# ELEC5550_Team_26_USB_Schematic.net
KiCad netlist of a schematic drawn in Altium Designer
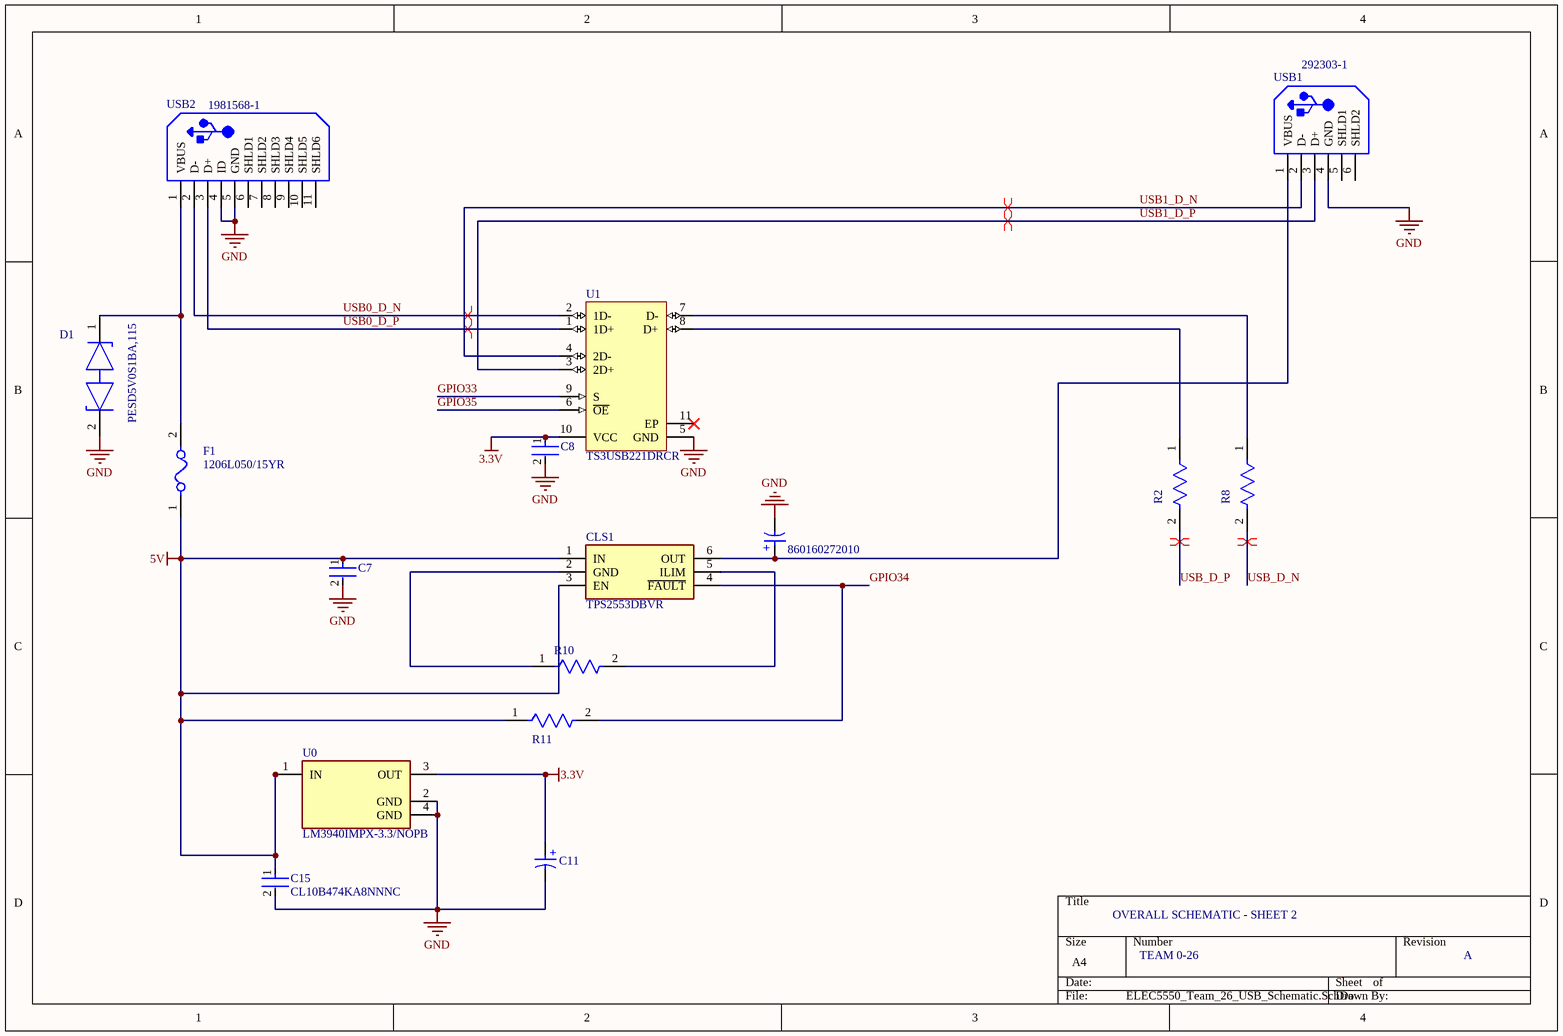
[diagram p0: ELEC5550_Team_26_USB_Schematic.SchDoc]

(export (version "E")
  (design (tool "Eeschema 10.0.6"))
  (components
    (comp (ref "C7")
      (value "CC0805KRX7R9BB104")
      (footprint "FP-CC0805-0_85-MFG")
      (description "CAP CER 0.1UF 50V X7R 0805")
      (fields (field (name "TOLERANCE") "0.1") (field (name "MANUFACTURER") "Yageo"))
      (libsource (lib "Altium Content Vault") (part "11868f565c42a9108669ba33697ecf6"))
    )
    (comp (ref "C8")
      (value "CC0805KRX7R9BB104")
      (footprint "FP-CC0805-0_85-MFG")
      (description "CAP CER 0.1UF 50V X7R 0805")
      (fields (field (name "TOLERANCE") "0.1") (field (name "MANUFACTURER") "Yageo"))
      (libsource (lib "Altium Content Vault") (part "11868f565c42a9108669ba33697ecf6"))
    )
    (comp (ref "C9")
      (value "860160272010")
      (footprint "WCAP-ATLL_D5H11")
      (description "860160272010 Cap, 120Uf, 10V, Alu Elec, Radial Rohs Compliant: Yes")
      (fields (field (name "TOLERANCE") "20%"))
      (libsource (lib "Altium Content Vault") (part "Capacitor_Polarized"))
    )
    (comp (ref "C11")
      (value "KS336M016C07RR0VH2FP0")
      (footprint "WCAP-ATLL_D5H11")
      (description "860160372005 Aluminium Electrolytic Capacitor-Leaded Rohs Compliant: Yes")
      (fields (field (name "TOLERANCE") "20%"))
      (libsource (lib "Altium Content Vault") (part "Capacitor_Polarized"))
    )
    (comp (ref "C15")
      (value "CL10B474KA8NNNC")
      (footprint "FP-GRM188-0_1-e0_2_0_5-MFG")
      (description "25V 470nF X7R ±10% 0603 Multilayer Ceramic Capacitors MLCC - SMD/SMT ROHS")
      (fields (field (name "TOLERANCE") "10%"))
      (libsource (lib "Altium Content Vault") (part "11868f565c42a9108669ba33697ecf6"))
    )
    (comp (ref "CLS1")
      (value "TPS2553DBVR")
      (footprint "SamacSys:SOT95P280X145-6N")
      (description "Integrated Circuit")
      (fields (field (name "MOUSER PART NUMBER") "595-TPS2553DBVR"))
      (libsource (lib "*") (part "TPS2553DBVR"))
    )
    (comp (ref "D1")
      (value "PESD5V0S1BA,115")
      (footprint "FP-SOD323-CA-MFG")
      (description "TVS DIODE 5V 14V SOD323")
      (libsource (lib "Altium Content Vault") (part "f6dbb2535d6b2d347ec798cb4d032a4"))
    )
    (comp (ref "F1")
      (value "1206L050/15YR")
      (footprint "FP-1206L-MFG")
      (description "PTC RESET FUSE 15V 500MA 1206")
      (fields
        (field (name "MANUFACTURER") "Littelfuse Inc")
        (field (name "OCTOPART") "https://octopart.com/1206l050%2F15yr-littelfuse-673645")
      )
      (libsource (lib "Altium Content Vault") (part "5bcf9b9f640e542cf0359d10258e979"))
    )
    (comp (ref "R2")
      (value "RC0603JR-0722RL")
      (footprint "FP-RC0603-0_55-IPC_C")
      (description "RES SMD 22 OHM 5% 1/10W 0603")
      (fields (field (name "TOLERANCE") "5%"))
      (libsource (lib "Altium Content Vault") (part "1029c3af85768c4190bb7ad29bc67b5"))
    )
    (comp (ref "R8")
      (value "RC0603JR-0722RL")
      (footprint "FP-RC0603-0_55-IPC_C")
      (description "RES SMD 22 OHM 5% 1/10W 0603")
      (fields (field (name "TOLERANCE") "5%"))
      (libsource (lib "Altium Content Vault") (part "1029c3af85768c4190bb7ad29bc67b5"))
    )
    (comp (ref "R10")
      (value "RCT0320KJLF")
      (footprint "FP-RT0603-MFG")
      (description "RT0603 20KΩ 0.1W 25 ppm/°C 0.10%")
      (fields (field (name "MANUFACTURER PART NUMBER") "RT0603BRD1320KL") (field (name "TOLERANCE") "0.001"))
      (libsource (lib "Altium Content Vault") (part "1029c3af85768c4190bb7ad29bc67b5"))
    )
    (comp (ref "R11")
      (value "RCT03100KJLF")
      (footprint "FP-AT0603-IPC_A")
      (libsource (lib "Altium Content Vault") (part "1029c3af85768c4190bb7ad29bc67b5"))
    )
    (comp (ref "U0")
      (value "LM3940IMPX-3.3/NOPB")
      (footprint "FP-DCY0004A-MFG")
      (description "IC REG LINEAR 3.3V 1A SOT223-4")
      (libsource (lib "Altium Content Vault") (part "c31ed432f589313beb2aec2175fc138"))
    )
    (comp (ref "U1")
      (value "TS3USB221DRCR")
      (footprint "DRC0010J_V")
      (fields (field (name "MANUFACTURER") "Texas Instruments"))
      (libsource (lib "Altium Content Vault") (part "TI-TS3USB221-SON_DRC-10"))
    )
    (comp (ref "USB1")
      (value "292303-1")
      (footprint "TE-292303-1_V")
      (fields (field (name "MANUFACTURER") "TE Connectivity"))
      (libsource (lib "Altium Content Vault") (part "USB-4-2SHLD"))
    )
    (comp (ref "USB2")
      (value "1981568-1")
      (footprint "TECO-1981568-5_V")
      (description "Micro USB Receptacle Standard Type B Assy, 5-Pin SMD, RoHS, Tape and Reel")
      (fields (field (name "MANUFACTURER") "TE Connectivity"))
      (libsource (lib "Altium Content Vault") (part "USB-5-6SHLD"))
    )
  )
  (nets
    (net (code "1") (name "/GPIO33") (class "Default")
      (node (ref "U1") (pin "9") (pinfunction "S_9") (pintype "input"))
    )
    (net (code "2") (name "/GPIO34") (class "Default")
      (node (ref "CLS1") (pin "4") (pinfunction "~{FAULT}_4") (pintype "passive"))
      (node (ref "R11") (pin "2") (pinfunction "2_2") (pintype "passive"))
    )
    (net (code "3") (name "/GPIO35") (class "Default")
      (node (ref "U1") (pin "6") (pinfunction "~{OE}_6") (pintype "input"))
    )
    (net (code "4") (name "/USB0_D_N") (class "Default")
      (node (ref "U1") (pin "2") (pinfunction "1D-_2") (pintype "bidirectional"))
      (node (ref "USB2") (pin "2") (pinfunction "D-_2") (pintype "passive"))
    )
    (net (code "5") (name "/USB0_D_P") (class "Default")
      (node (ref "U1") (pin "1") (pinfunction "1D+_1") (pintype "bidirectional"))
      (node (ref "USB2") (pin "3") (pinfunction "D+_3") (pintype "passive"))
    )
    (net (code "6") (name "/USB1_D_N") (class "Default")
      (node (ref "U1") (pin "4") (pinfunction "2D-_4") (pintype "bidirectional"))
      (node (ref "USB1") (pin "2") (pinfunction "D-_2") (pintype "passive"))
    )
    (net (code "7") (name "/USB1_D_P") (class "Default")
      (node (ref "U1") (pin "3") (pinfunction "2D+_3") (pintype "bidirectional"))
      (node (ref "USB1") (pin "3") (pinfunction "D+_3") (pintype "passive"))
    )
    (net (code "8") (name "/USB_D_N") (class "Default")
      (node (ref "R8") (pin "2") (pinfunction "2_2") (pintype "passive"))
    )
    (net (code "9") (name "/USB_D_P") (class "Default")
      (node (ref "R2") (pin "2") (pinfunction "2_2") (pintype "passive"))
    )
    (net (code "10") (name "3.3V") (class "Default")
      (node (ref "C11") (pin "1") (pinfunction "P_1") (pintype "passive"))
      (node (ref "C8") (pin "1") (pinfunction "1_1") (pintype "passive"))
      (node (ref "U0") (pin "3") (pinfunction "OUT_3") (pintype "passive"))
      (node (ref "U1") (pin "10") (pinfunction "VCC_10") (pintype "power_in"))
    )
    (net (code "11") (name "5V") (class "Default")
      (node (ref "C15") (pin "1") (pinfunction "1_1") (pintype "passive"))
      (node (ref "C7") (pin "1") (pinfunction "1_1") (pintype "passive"))
      (node (ref "CLS1") (pin "1") (pinfunction "IN_1") (pintype "passive"))
      (node (ref "CLS1") (pin "3") (pinfunction "EN_3") (pintype "passive"))
      (node (ref "F1") (pin "1") (pinfunction "1_1") (pintype "passive"))
      (node (ref "R11") (pin "1") (pinfunction "1_1") (pintype "passive"))
      (node (ref "U0") (pin "1") (pinfunction "IN_1") (pintype "power_in"))
    )
    (net (code "12") (name "GND") (class "Default")
      (node (ref "C11") (pin "2") (pinfunction "N_2") (pintype "passive"))
      (node (ref "C15") (pin "2") (pinfunction "2_2") (pintype "passive"))
      (node (ref "C7") (pin "2") (pinfunction "2_2") (pintype "passive"))
      (node (ref "C8") (pin "2") (pinfunction "2_2") (pintype "passive"))
      (node (ref "C9") (pin "2") (pinfunction "N_2") (pintype "passive"))
      (node (ref "D1") (pin "2") (pinfunction "K2_2") (pintype "passive"))
      (node (ref "U0") (pin "2") (pinfunction "GND_2") (pintype "power_in"))
      (node (ref "U0") (pin "4") (pinfunction "GND_4") (pintype "power_in"))
      (node (ref "U1") (pin "5") (pinfunction "GND_5") (pintype "power_in"))
      (node (ref "USB1") (pin "4") (pinfunction "GND_4") (pintype "passive"))
      (node (ref "USB2") (pin "4") (pinfunction "ID_4") (pintype "passive"))
      (node (ref "USB2") (pin "5") (pinfunction "GND_5") (pintype "passive"))
    )
    (net (code "13") (name "Net-(C9-P)") (class "Default")
      (node (ref "C9") (pin "1") (pinfunction "P_1") (pintype "passive"))
      (node (ref "CLS1") (pin "6") (pinfunction "OUT_6") (pintype "passive"))
      (node (ref "USB1") (pin "1") (pinfunction "VBUS_1") (pintype "passive"))
    )
    (net (code "14") (name "Net-(CLS1-GND)") (class "Default")
      (node (ref "CLS1") (pin "2") (pinfunction "GND_2") (pintype "passive"))
      (node (ref "R10") (pin "1") (pinfunction "1_1") (pintype "passive"))
    )
    (net (code "15") (name "Net-(CLS1-ILIM)") (class "Default")
      (node (ref "CLS1") (pin "5") (pinfunction "ILIM_5") (pintype "passive"))
      (node (ref "R10") (pin "2") (pinfunction "2_2") (pintype "passive"))
    )
    (net (code "16") (name "Net-(D1-K1)") (class "Default")
      (node (ref "D1") (pin "1") (pinfunction "K1_1") (pintype "passive"))
      (node (ref "F1") (pin "2") (pinfunction "2_2") (pintype "passive"))
      (node (ref "USB2") (pin "1") (pinfunction "VBUS_1") (pintype "passive"))
    )
    (net (code "17") (name "Net-(U1-D+)") (class "Default")
      (node (ref "R2") (pin "1") (pinfunction "1_1") (pintype "passive"))
      (node (ref "U1") (pin "8") (pinfunction "D+_8") (pintype "bidirectional"))
    )
    (net (code "18") (name "Net-(U1-D-)") (class "Default")
      (node (ref "R8") (pin "1") (pinfunction "1_1") (pintype "passive"))
      (node (ref "U1") (pin "7") (pinfunction "D-_7") (pintype "bidirectional"))
    )
    (net (code "19") (name "unconnected-(U1-EP-Pad11)") (class "Default")
      (node (ref "U1") (pin "11") (pinfunction "EP_11") (pintype "passive+no_connect"))
    )
    (net (code "20") (name "unconnected-(USB1-SHLD1-Pad5)") (class "Default")
      (node (ref "USB1") (pin "5") (pinfunction "SHLD1_5") (pintype "passive"))
    )
    (net (code "21") (name "unconnected-(USB1-SHLD2-Pad6)") (class "Default")
      (node (ref "USB1") (pin "6") (pinfunction "SHLD2_6") (pintype "passive"))
    )
    (net (code "22") (name "unconnected-(USB2-SHLD1-Pad6)") (class "Default")
      (node (ref "USB2") (pin "6") (pinfunction "SHLD1_6") (pintype "passive"))
    )
    (net (code "23") (name "unconnected-(USB2-SHLD2-Pad7)") (class "Default")
      (node (ref "USB2") (pin "7") (pinfunction "SHLD2_7") (pintype "passive"))
    )
    (net (code "24") (name "unconnected-(USB2-SHLD3-Pad8)") (class "Default")
      (node (ref "USB2") (pin "8") (pinfunction "SHLD3_8") (pintype "passive"))
    )
    (net (code "25") (name "unconnected-(USB2-SHLD4-Pad9)") (class "Default")
      (node (ref "USB2") (pin "9") (pinfunction "SHLD4_9") (pintype "passive"))
    )
    (net (code "26") (name "unconnected-(USB2-SHLD5-Pad10)") (class "Default")
      (node (ref "USB2") (pin "10") (pinfunction "SHLD5_10") (pintype "passive"))
    )
    (net (code "27") (name "unconnected-(USB2-SHLD6-Pad11)") (class "Default")
      (node (ref "USB2") (pin "11") (pinfunction "SHLD6_11") (pintype "passive"))
    )
  )
)
